# REBEL_LED_driver.net
KiCad netlist of a schematic drawn in EAGLE
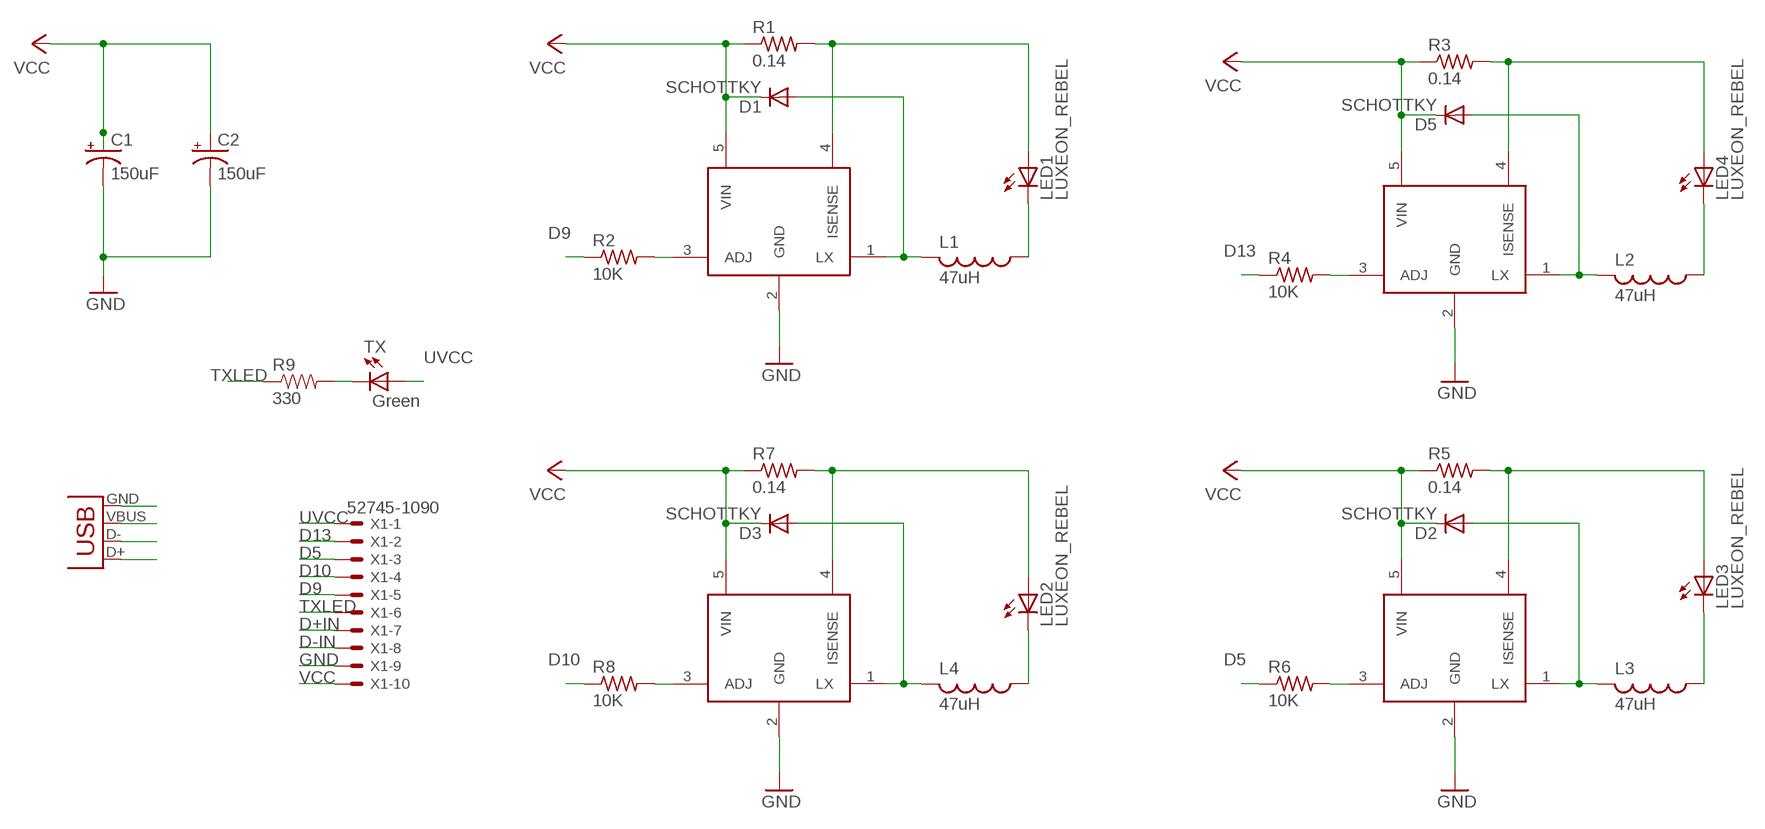
[diagram p0: schematic, sheet 1]

(export (version "E")
  (design (tool "Eeschema 10.0.6"))
  (components
    (comp (ref "C1")
      (value "150uF")
      (footprint "eagle-import:175TMP-0810")
      (libsource (lib "eagle-import") (part "CPOL-US175TMP-0810"))
    )
    (comp (ref "C2")
      (value "150uF")
      (footprint "eagle-import:175TMP-0810")
      (libsource (lib "eagle-import") (part "CPOL-US175TMP-0810"))
    )
    (comp (ref "D1")
      (value "SCHOTTKY")
      (footprint "eagle-import:DO214AC")
      (libsource (lib "eagle-import") (part "DIODE-DO214AC"))
    )
    (comp (ref "D2")
      (value "SCHOTTKY")
      (footprint "eagle-import:DO214AC")
      (libsource (lib "eagle-import") (part "DIODE-DO214AC"))
    )
    (comp (ref "D3")
      (value "SCHOTTKY")
      (footprint "eagle-import:DO214AC")
      (libsource (lib "eagle-import") (part "DIODE-DO214AC"))
    )
    (comp (ref "D5")
      (value "SCHOTTKY")
      (footprint "eagle-import:DO214AC")
      (libsource (lib "eagle-import") (part "DIODE-DO214AC"))
    )
    (comp (ref "L1")
      (value "47uH")
      (footprint "eagle-import:TDK6045")
      (libsource (lib "eagle-import") (part "L-US"))
    )
    (comp (ref "L2")
      (value "47uH")
      (footprint "eagle-import:TDK6045")
      (libsource (lib "eagle-import") (part "L-US"))
    )
    (comp (ref "L3")
      (value "47uH")
      (footprint "eagle-import:TDK6045")
      (libsource (lib "eagle-import") (part "L-US"))
    )
    (comp (ref "L4")
      (value "47uH")
      (footprint "eagle-import:TDK6045")
      (libsource (lib "eagle-import") (part "L-US"))
    )
    (comp (ref "LED1")
      (value "LUXEON_REBEL")
      (footprint "eagle-import:LUXEON_REBEL")
      (libsource (lib "eagle-import") (part "LUXEON_REBEL"))
    )
    (comp (ref "LED2")
      (value "LUXEON_REBEL")
      (footprint "eagle-import:LUXEON_REBEL")
      (libsource (lib "eagle-import") (part "LUXEON_REBEL"))
    )
    (comp (ref "LED3")
      (value "LUXEON_REBEL")
      (footprint "eagle-import:LUXEON_REBEL")
      (libsource (lib "eagle-import") (part "LUXEON_REBEL"))
    )
    (comp (ref "LED4")
      (value "LUXEON_REBEL")
      (footprint "eagle-import:LUXEON_REBEL")
      (libsource (lib "eagle-import") (part "LUXEON_REBEL"))
    )
    (comp (ref "R1")
      (value "0.14")
      (footprint "eagle-import:R0805")
      (libsource (lib "eagle-import") (part "R-US_R0805"))
    )
    (comp (ref "R2")
      (value "10K")
      (footprint "eagle-import:R0603")
      (libsource (lib "eagle-import") (part "R-US_R0603"))
    )
    (comp (ref "R3")
      (value "0.14")
      (footprint "eagle-import:R0805")
      (libsource (lib "eagle-import") (part "R-US_R0805"))
    )
    (comp (ref "R4")
      (value "10K")
      (footprint "eagle-import:R0603")
      (libsource (lib "eagle-import") (part "R-US_R0603"))
    )
    (comp (ref "R5")
      (value "0.14")
      (footprint "eagle-import:R0805")
      (libsource (lib "eagle-import") (part "R-US_R0805"))
    )
    (comp (ref "R6")
      (value "10K")
      (footprint "eagle-import:R0603")
      (libsource (lib "eagle-import") (part "R-US_R0603"))
    )
    (comp (ref "R7")
      (value "0.14")
      (footprint "eagle-import:R0805")
      (libsource (lib "eagle-import") (part "R-US_R0805"))
    )
    (comp (ref "R8")
      (value "10K")
      (footprint "eagle-import:R0603")
      (libsource (lib "eagle-import") (part "R-US_R0603"))
    )
    (comp (ref "R9")
      (value "330")
      (footprint "eagle-import:0402-RES")
      (libsource (lib "eagle-import") (part "RESISTOR0402-RES"))
    )
    (comp (ref "TX")
      (value "Green")
      (footprint "eagle-import:LED-0603")
      (libsource (lib "eagle-import") (part "LED0603"))
    )
    (comp (ref "U$2")
      (value "ZLED7000-LEDDRIVER")
      (footprint "eagle-import:SOT89-5")
      (libsource (lib "eagle-import") (part "ZLED7000-LEDDRIVER"))
    )
    (comp (ref "U$3")
      (value "ZLED7000-LEDDRIVER")
      (footprint "eagle-import:SOT89-5")
      (libsource (lib "eagle-import") (part "ZLED7000-LEDDRIVER"))
    )
    (comp (ref "U$4")
      (value "ZLED7000-LEDDRIVER")
      (footprint "eagle-import:SOT89-5")
      (libsource (lib "eagle-import") (part "ZLED7000-LEDDRIVER"))
    )
    (comp (ref "U$6")
      (value "ZLED7000-LEDDRIVER")
      (footprint "eagle-import:SOT89-5")
      (libsource (lib "eagle-import") (part "ZLED7000-LEDDRIVER"))
    )
    (comp (ref "X1")
      (value "52745-1090")
      (footprint "eagle-import:52745-1090")
      (libsource (lib "eagle-import") (part "52745-1090"))
    )
    (comp (ref "X2")
      (value "USB-MICROB")
      (footprint "eagle-import:USB-MICROB")
      (libsource (lib "eagle-import") (part "USB-MICROB"))
    )
  )
  (nets
    (net (code "1") (name "/D+IN") (class "Default")
      (node (ref "X1") (pin "7") (pinfunction "S_7") (pintype "passive"))
      (node (ref "X2") (pin "D+") (pinfunction "D+_D+") (pintype "bidirectional"))
    )
    (net (code "2") (name "/D-IN") (class "Default")
      (node (ref "X1") (pin "8") (pinfunction "S_8") (pintype "passive"))
      (node (ref "X2") (pin "D-") (pinfunction "D-_D-") (pintype "bidirectional"))
    )
    (net (code "3") (name "/D5") (class "Default")
      (node (ref "R6") (pin "1") (pinfunction "1_1") (pintype "passive"))
      (node (ref "X1") (pin "3") (pinfunction "S_3") (pintype "passive"))
    )
    (net (code "4") (name "/D9") (class "Default")
      (node (ref "R2") (pin "1") (pinfunction "1_1") (pintype "passive"))
      (node (ref "X1") (pin "5") (pinfunction "S_5") (pintype "passive"))
    )
    (net (code "5") (name "/D10") (class "Default")
      (node (ref "R8") (pin "1") (pinfunction "1_1") (pintype "passive"))
      (node (ref "X1") (pin "4") (pinfunction "S_4") (pintype "passive"))
    )
    (net (code "6") (name "/D13") (class "Default")
      (node (ref "R4") (pin "1") (pinfunction "1_1") (pintype "passive"))
      (node (ref "X1") (pin "2") (pinfunction "S_2") (pintype "passive"))
    )
    (net (code "7") (name "/TXLED") (class "Default")
      (node (ref "R9") (pin "1") (pinfunction "1_1") (pintype "passive"))
      (node (ref "X1") (pin "6") (pinfunction "S_6") (pintype "passive"))
    )
    (net (code "8") (name "/UVCC") (class "Default")
      (node (ref "TX") (pin "A") (pinfunction "A_A") (pintype "passive"))
      (node (ref "X1") (pin "1") (pinfunction "S_1") (pintype "passive"))
      (node (ref "X2") (pin "VBUS") (pinfunction "VBUS_VBUS") (pintype "bidirectional"))
    )
    (net (code "9") (name "GND") (class "Default")
      (node (ref "C1") (pin "-") (pinfunction "-_-") (pintype "passive"))
      (node (ref "C2") (pin "-") (pinfunction "-_-") (pintype "passive"))
      (node (ref "U$2") (pin "2") (pinfunction "GND_2") (pintype "bidirectional"))
      (node (ref "U$3") (pin "2") (pinfunction "GND_2") (pintype "bidirectional"))
      (node (ref "U$4") (pin "2") (pinfunction "GND_2") (pintype "bidirectional"))
      (node (ref "U$6") (pin "2") (pinfunction "GND_2") (pintype "bidirectional"))
      (node (ref "X1") (pin "9") (pinfunction "S_9") (pintype "passive"))
      (node (ref "X2") (pin "GND") (pinfunction "GND_GND") (pintype "bidirectional"))
    )
    (net (code "10") (name "Net-(L1-Pad1)") (class "Default")
      (node (ref "L1") (pin "1") (pinfunction "1_1") (pintype "passive"))
      (node (ref "LED1") (pin "C") (pinfunction "C_C") (pintype "passive"))
      (node (ref "LED1") (pin "C@1") (pinfunction "C_C@1") (pintype "passive"))
    )
    (net (code "11") (name "Net-(L2-Pad1)") (class "Default")
      (node (ref "L2") (pin "1") (pinfunction "1_1") (pintype "passive"))
      (node (ref "LED4") (pin "C") (pinfunction "C_C") (pintype "passive"))
      (node (ref "LED4") (pin "C@1") (pinfunction "C_C@1") (pintype "passive"))
    )
    (net (code "12") (name "Net-(L3-Pad1)") (class "Default")
      (node (ref "L3") (pin "1") (pinfunction "1_1") (pintype "passive"))
      (node (ref "LED3") (pin "C") (pinfunction "C_C") (pintype "passive"))
      (node (ref "LED3") (pin "C@1") (pinfunction "C_C@1") (pintype "passive"))
    )
    (net (code "13") (name "Net-(L4-Pad1)") (class "Default")
      (node (ref "L4") (pin "1") (pinfunction "1_1") (pintype "passive"))
      (node (ref "LED2") (pin "C") (pinfunction "C_C") (pintype "passive"))
      (node (ref "LED2") (pin "C@1") (pinfunction "C_C@1") (pintype "passive"))
    )
    (net (code "14") (name "Net-(R9-Pad2)") (class "Default")
      (node (ref "R9") (pin "2") (pinfunction "2_2") (pintype "passive"))
      (node (ref "TX") (pin "C") (pinfunction "C_C") (pintype "passive"))
    )
    (net (code "15") (name "Net-(U$2-ADJ)") (class "Default")
      (node (ref "R2") (pin "2") (pinfunction "2_2") (pintype "passive"))
      (node (ref "U$2") (pin "3") (pinfunction "ADJ_3") (pintype "bidirectional"))
    )
    (net (code "16") (name "Net-(U$2-ISENSE)") (class "Default")
      (node (ref "LED1") (pin "A") (pinfunction "A_A") (pintype "passive"))
      (node (ref "LED1") (pin "A@1") (pinfunction "A_A@1") (pintype "passive"))
      (node (ref "R1") (pin "2") (pinfunction "2_2") (pintype "passive"))
      (node (ref "U$2") (pin "4") (pinfunction "ISENSE_4") (pintype "bidirectional"))
    )
    (net (code "17") (name "Net-(U$2-LX)") (class "Default")
      (node (ref "D1") (pin "A") (pinfunction "A_A") (pintype "passive"))
      (node (ref "L1") (pin "2") (pinfunction "2_2") (pintype "passive"))
      (node (ref "U$2") (pin "1") (pinfunction "LX_1") (pintype "bidirectional"))
    )
    (net (code "18") (name "Net-(U$3-ADJ)") (class "Default")
      (node (ref "R6") (pin "2") (pinfunction "2_2") (pintype "passive"))
      (node (ref "U$3") (pin "3") (pinfunction "ADJ_3") (pintype "bidirectional"))
    )
    (net (code "19") (name "Net-(U$3-ISENSE)") (class "Default")
      (node (ref "LED3") (pin "A") (pinfunction "A_A") (pintype "passive"))
      (node (ref "LED3") (pin "A@1") (pinfunction "A_A@1") (pintype "passive"))
      (node (ref "R5") (pin "2") (pinfunction "2_2") (pintype "passive"))
      (node (ref "U$3") (pin "4") (pinfunction "ISENSE_4") (pintype "bidirectional"))
    )
    (net (code "20") (name "Net-(U$3-LX)") (class "Default")
      (node (ref "D2") (pin "A") (pinfunction "A_A") (pintype "passive"))
      (node (ref "L3") (pin "2") (pinfunction "2_2") (pintype "passive"))
      (node (ref "U$3") (pin "1") (pinfunction "LX_1") (pintype "bidirectional"))
    )
    (net (code "21") (name "Net-(U$4-ADJ)") (class "Default")
      (node (ref "R8") (pin "2") (pinfunction "2_2") (pintype "passive"))
      (node (ref "U$4") (pin "3") (pinfunction "ADJ_3") (pintype "bidirectional"))
    )
    (net (code "22") (name "Net-(U$4-ISENSE)") (class "Default")
      (node (ref "LED2") (pin "A") (pinfunction "A_A") (pintype "passive"))
      (node (ref "LED2") (pin "A@1") (pinfunction "A_A@1") (pintype "passive"))
      (node (ref "R7") (pin "2") (pinfunction "2_2") (pintype "passive"))
      (node (ref "U$4") (pin "4") (pinfunction "ISENSE_4") (pintype "bidirectional"))
    )
    (net (code "23") (name "Net-(U$4-LX)") (class "Default")
      (node (ref "D3") (pin "A") (pinfunction "A_A") (pintype "passive"))
      (node (ref "L4") (pin "2") (pinfunction "2_2") (pintype "passive"))
      (node (ref "U$4") (pin "1") (pinfunction "LX_1") (pintype "bidirectional"))
    )
    (net (code "24") (name "Net-(U$6-ADJ)") (class "Default")
      (node (ref "R4") (pin "2") (pinfunction "2_2") (pintype "passive"))
      (node (ref "U$6") (pin "3") (pinfunction "ADJ_3") (pintype "bidirectional"))
    )
    (net (code "25") (name "Net-(U$6-ISENSE)") (class "Default")
      (node (ref "LED4") (pin "A") (pinfunction "A_A") (pintype "passive"))
      (node (ref "LED4") (pin "A@1") (pinfunction "A_A@1") (pintype "passive"))
      (node (ref "R3") (pin "2") (pinfunction "2_2") (pintype "passive"))
      (node (ref "U$6") (pin "4") (pinfunction "ISENSE_4") (pintype "bidirectional"))
    )
    (net (code "26") (name "Net-(U$6-LX)") (class "Default")
      (node (ref "D5") (pin "A") (pinfunction "A_A") (pintype "passive"))
      (node (ref "L2") (pin "2") (pinfunction "2_2") (pintype "passive"))
      (node (ref "U$6") (pin "1") (pinfunction "LX_1") (pintype "bidirectional"))
    )
    (net (code "27") (name "VCC") (class "Default")
      (node (ref "C1") (pin "+") (pinfunction "+_+") (pintype "passive"))
      (node (ref "C2") (pin "+") (pinfunction "+_+") (pintype "passive"))
      (node (ref "D1") (pin "C") (pinfunction "C_C") (pintype "passive"))
      (node (ref "D2") (pin "C") (pinfunction "C_C") (pintype "passive"))
      (node (ref "D3") (pin "C") (pinfunction "C_C") (pintype "passive"))
      (node (ref "D5") (pin "C") (pinfunction "C_C") (pintype "passive"))
      (node (ref "R1") (pin "1") (pinfunction "1_1") (pintype "passive"))
      (node (ref "R3") (pin "1") (pinfunction "1_1") (pintype "passive"))
      (node (ref "R5") (pin "1") (pinfunction "1_1") (pintype "passive"))
      (node (ref "R7") (pin "1") (pinfunction "1_1") (pintype "passive"))
      (node (ref "U$2") (pin "5") (pinfunction "VIN_5") (pintype "bidirectional"))
      (node (ref "U$3") (pin "5") (pinfunction "VIN_5") (pintype "bidirectional"))
      (node (ref "U$4") (pin "5") (pinfunction "VIN_5") (pintype "bidirectional"))
      (node (ref "U$6") (pin "5") (pinfunction "VIN_5") (pintype "bidirectional"))
      (node (ref "X1") (pin "10") (pinfunction "S_10") (pintype "passive"))
    )
  )
)
